# Watchdog.net
KiCad netlist of a schematic drawn in EasyEDA Pro
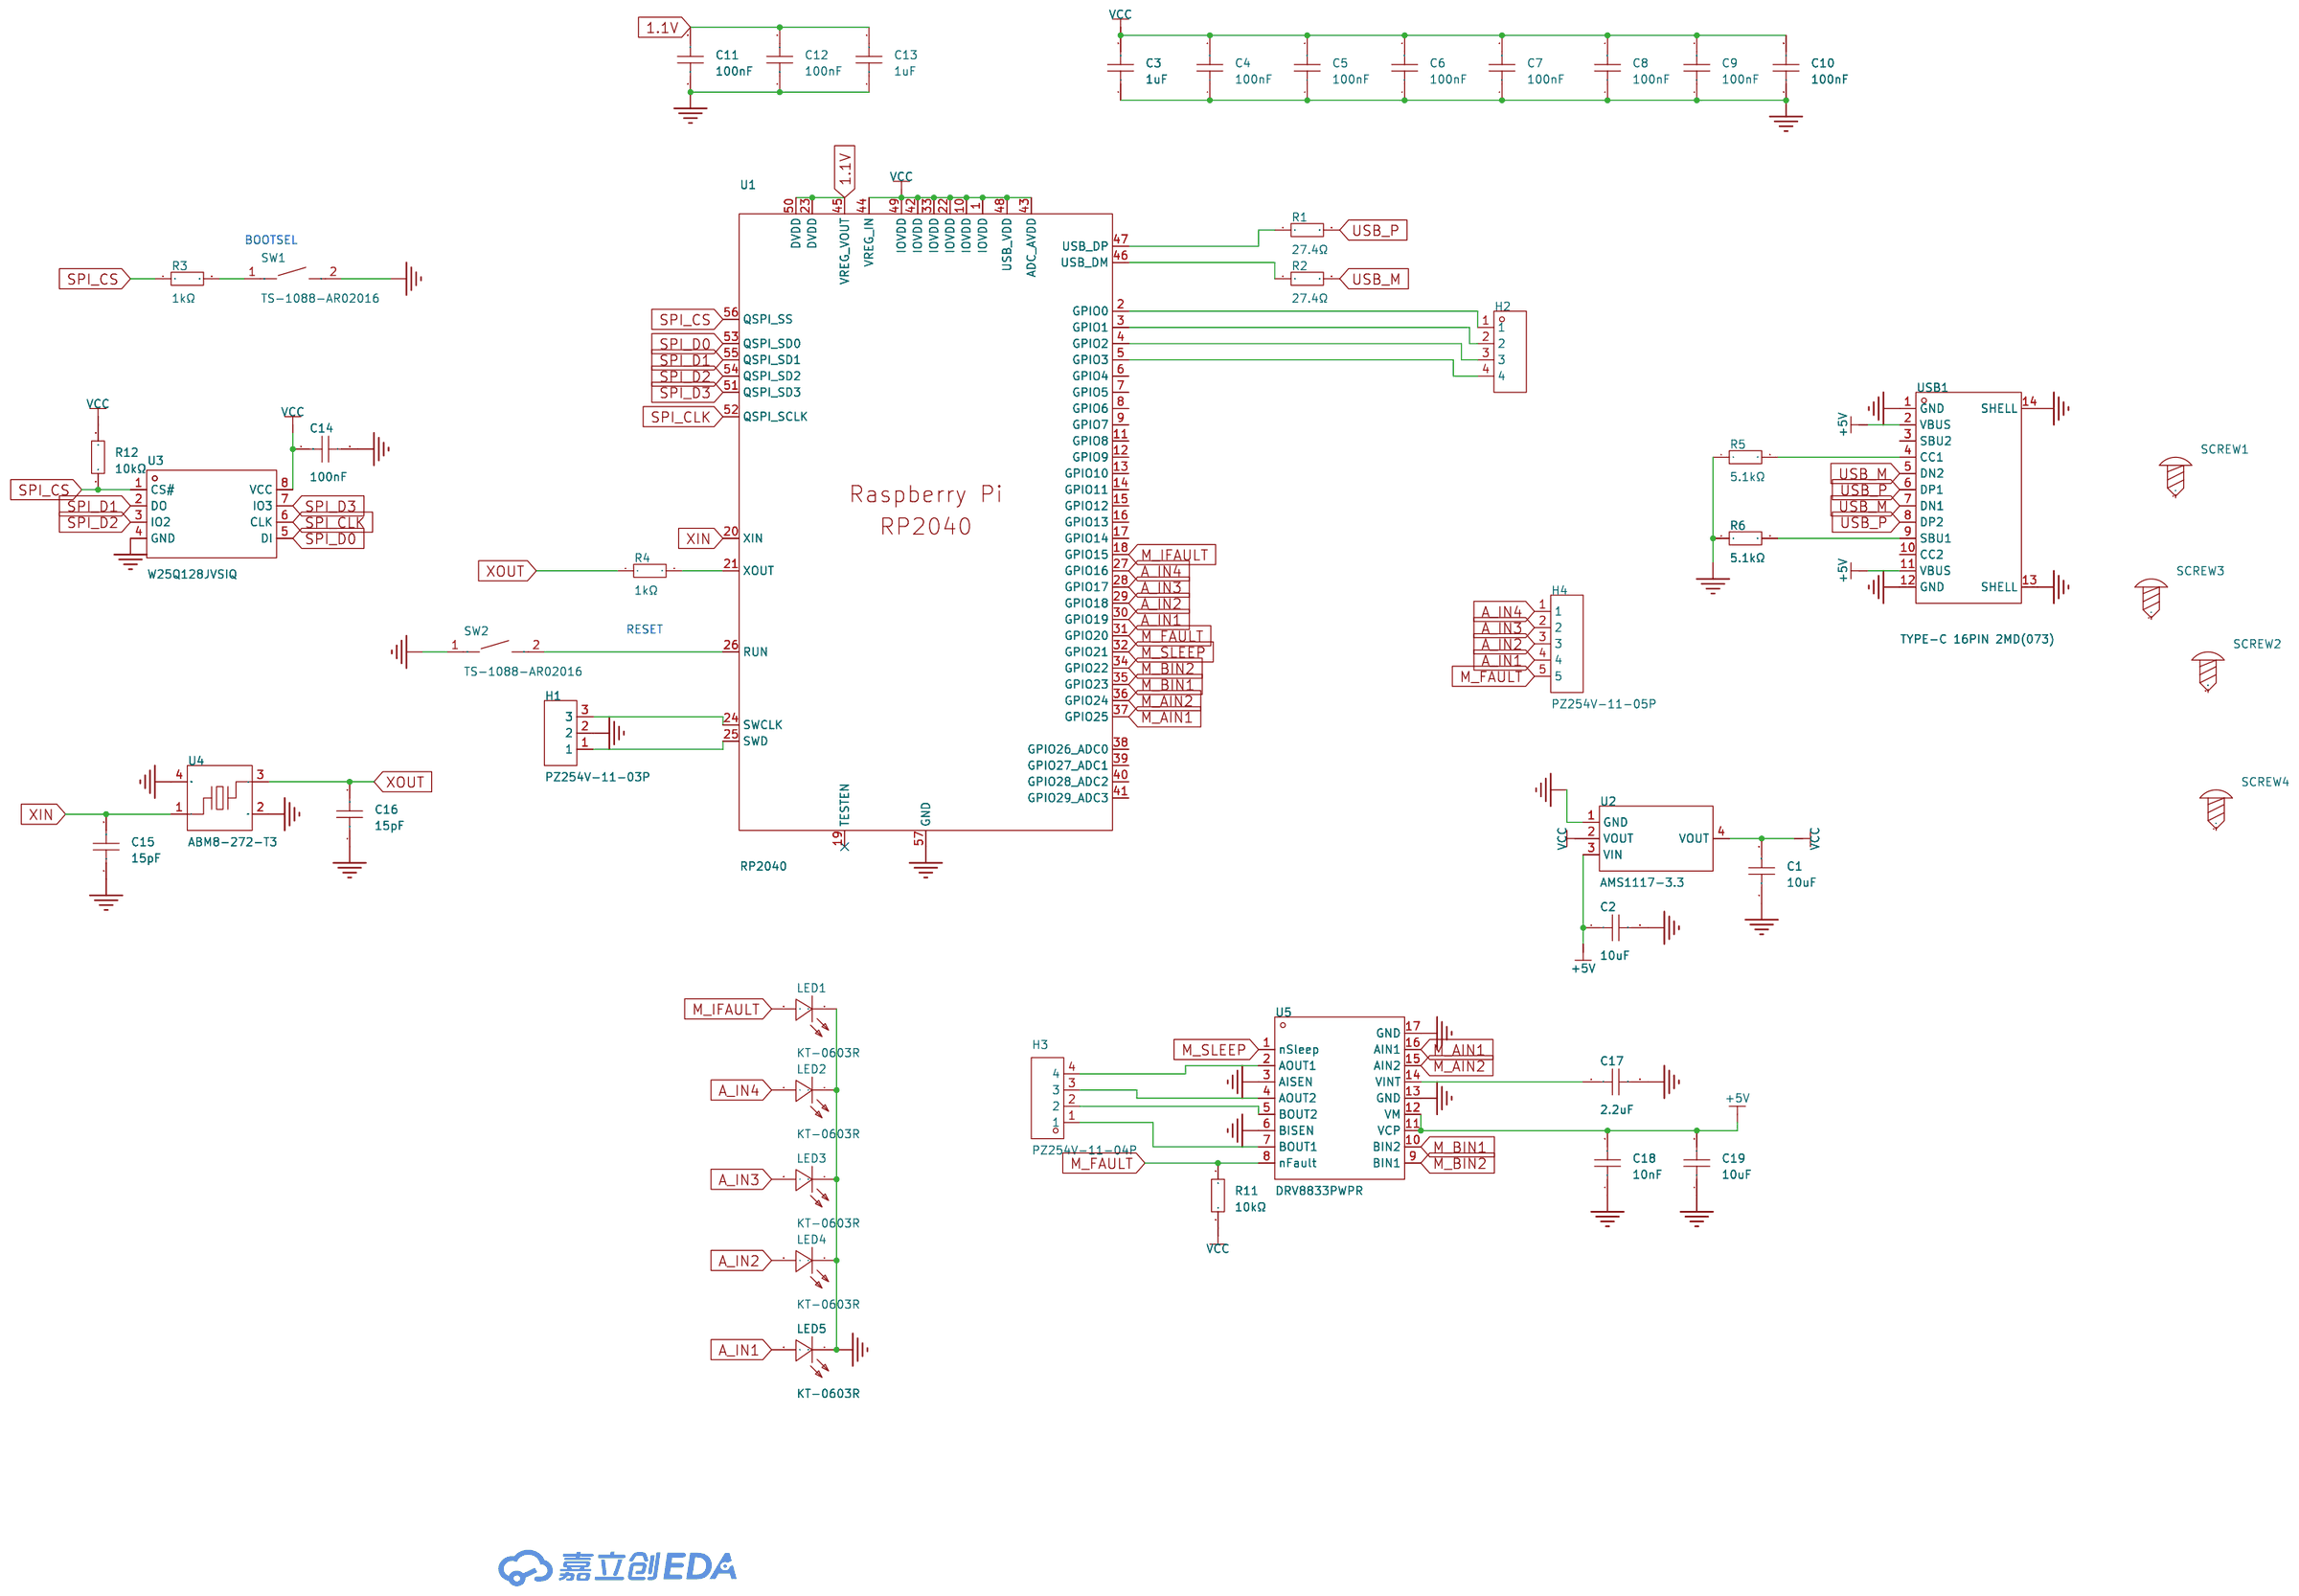
[diagram p0: schematic sheet]

(export (version "E")
  (design (tool "Eeschema 10.0.6"))
  (components
    (comp (ref "C1")
      (value "10uF")
      (footprint "easyedapro:C0603")
      (fields
        (field (name "Manufacturer Part") "CL05A106MQ5NUNC")
        (field (name "Manufacturer") "SAMSUNG(三星)")
      )
      (libsource (lib "easyedapro") (part "CapAcitance"))
    )
    (comp (ref "C2")
      (value "10uF")
      (footprint "easyedapro:C0603")
      (fields
        (field (name "Manufacturer Part") "CL05A106MQ5NUNC")
        (field (name "Manufacturer") "SAMSUNG(三星)")
      )
      (libsource (lib "easyedapro") (part "CapAcitance"))
    )
    (comp (ref "C3")
      (value "1uF")
      (footprint "easyedapro:C0603")
      (fields
        (field (name "Manufacturer Part") "CL05A105KA5NQNC")
        (field (name "Manufacturer") "SAMSUNG(三星)")
      )
      (libsource (lib "easyedapro") (part "CapAcitance"))
    )
    (comp (ref "C4")
      (value "100nF")
      (footprint "easyedapro:C0603")
      (fields
        (field (name "Manufacturer Part") "CL05B104KB54PNC")
        (field (name "Manufacturer") "SAMSUNG(三星)")
      )
      (libsource (lib "easyedapro") (part "CapAcitance"))
    )
    (comp (ref "C5")
      (value "100nF")
      (footprint "easyedapro:C0603")
      (fields
        (field (name "Manufacturer Part") "CL05B104KB54PNC")
        (field (name "Manufacturer") "SAMSUNG(三星)")
      )
      (libsource (lib "easyedapro") (part "CapAcitance"))
    )
    (comp (ref "C6")
      (value "100nF")
      (footprint "easyedapro:C0603")
      (fields
        (field (name "Manufacturer Part") "CL05B104KB54PNC")
        (field (name "Manufacturer") "SAMSUNG(三星)")
      )
      (libsource (lib "easyedapro") (part "CapAcitance"))
    )
    (comp (ref "C7")
      (value "100nF")
      (footprint "easyedapro:C0603")
      (fields
        (field (name "Manufacturer Part") "CL05B104KB54PNC")
        (field (name "Manufacturer") "SAMSUNG(三星)")
      )
      (libsource (lib "easyedapro") (part "CapAcitance"))
    )
    (comp (ref "C8")
      (value "100nF")
      (footprint "easyedapro:C0603")
      (fields
        (field (name "Manufacturer Part") "CL05B104KB54PNC")
        (field (name "Manufacturer") "SAMSUNG(三星)")
      )
      (libsource (lib "easyedapro") (part "CapAcitance"))
    )
    (comp (ref "C9")
      (value "100nF")
      (footprint "easyedapro:C0603")
      (fields
        (field (name "Manufacturer Part") "CL05B104KB54PNC")
        (field (name "Manufacturer") "SAMSUNG(三星)")
      )
      (libsource (lib "easyedapro") (part "CapAcitance"))
    )
    (comp (ref "C10")
      (value "100nF")
      (footprint "easyedapro:C0603")
      (fields
        (field (name "Manufacturer Part") "CL05B104KB54PNC")
        (field (name "Manufacturer") "SAMSUNG(三星)")
      )
      (libsource (lib "easyedapro") (part "CapAcitance"))
    )
    (comp (ref "C11")
      (value "100nF")
      (footprint "easyedapro:C0603")
      (fields
        (field (name "Manufacturer Part") "CL05B104KB54PNC")
        (field (name "Manufacturer") "SAMSUNG(三星)")
      )
      (libsource (lib "easyedapro") (part "CapAcitance"))
    )
    (comp (ref "C12")
      (value "100nF")
      (footprint "easyedapro:C0603")
      (fields
        (field (name "Manufacturer Part") "CL05B104KB54PNC")
        (field (name "Manufacturer") "SAMSUNG(三星)")
      )
      (libsource (lib "easyedapro") (part "CapAcitance"))
    )
    (comp (ref "C13")
      (value "1uF")
      (footprint "easyedapro:C0603")
      (fields
        (field (name "Manufacturer Part") "CL05A105KA5NQNC")
        (field (name "Manufacturer") "SAMSUNG(三星)")
      )
      (libsource (lib "easyedapro") (part "CapAcitance"))
    )
    (comp (ref "C14")
      (value "100nF")
      (footprint "easyedapro:C0603")
      (fields
        (field (name "Manufacturer Part") "CL05B104KB54PNC")
        (field (name "Manufacturer") "SAMSUNG(三星)")
      )
      (libsource (lib "easyedapro") (part "CapAcitance"))
    )
    (comp (ref "C15")
      (value "15pF")
      (footprint "easyedapro:C0603")
      (fields (field (name "Manufacturer Part") "0402CG150J500NT") (field (name "Manufacturer") "FH(风华)"))
      (libsource (lib "easyedapro") (part "CapAcitance"))
    )
    (comp (ref "C16")
      (value "15pF")
      (footprint "easyedapro:C0603")
      (fields (field (name "Manufacturer Part") "0402CG150J500NT") (field (name "Manufacturer") "FH(风华)"))
      (libsource (lib "easyedapro") (part "CapAcitance"))
    )
    (comp (ref "C17")
      (value "2.2uF")
      (footprint "easyedapro:C0603")
      (fields
        (field (name "Manufacturer Part") "CL05A225MQ5NSNC")
        (field (name "Manufacturer") "SAMSUNG(三星)")
      )
      (libsource (lib "easyedapro") (part "CapAcitance"))
    )
    (comp (ref "C18")
      (value "10nF")
      (footprint "easyedapro:C0603")
      (fields
        (field (name "Manufacturer Part") "CL05B103KB5NNNC")
        (field (name "Manufacturer") "SAMSUNG(三星)")
      )
      (libsource (lib "easyedapro") (part "CapAcitance"))
    )
    (comp (ref "C19")
      (value "10uF")
      (footprint "easyedapro:C0603")
      (fields
        (field (name "Manufacturer Part") "CL05A106MQ5NUNC")
        (field (name "Manufacturer") "SAMSUNG(三星)")
      )
      (libsource (lib "easyedapro") (part "CapAcitance"))
    )
    (comp (ref "H1")
      (value "PZ254V-11-03P")
      (footprint "easyedapro:HDR-TH_3P-P2.54-V-M")
      (fields (field (name "Manufacturer") "XFCN(兴飞)"))
      (libsource (lib "easyedapro") (part "PZ254V-11-03P_C2937625"))
    )
    (comp (ref "H2")
      (value "PZ254V-11-04P")
      (footprint "easyedapro:HDR-TH_4P-P2.54-V-M")
      (fields (field (name "Manufacturer") "XFCN(兴飞)"))
      (libsource (lib "easyedapro") (part "PZ254V-11-04P_C2691448"))
    )
    (comp (ref "H3")
      (value "PZ254V-11-04P")
      (footprint "easyedapro:HDR-TH_4P-P2.54-V-M")
      (fields (field (name "Manufacturer") "XFCN(兴飞)"))
      (libsource (lib "easyedapro") (part "PZ254V-11-04P_C2691448"))
    )
    (comp (ref "H4")
      (value "PZ254V-11-05P")
      (footprint "easyedapro:HDR-TH_5P-P2.54-V-M")
      (fields (field (name "Manufacturer") "XFCN(兴飞)"))
      (libsource (lib "easyedapro") (part "PZ254V-11-05P"))
    )
    (comp (ref "LED1")
      (value "KT-0603R")
      (footprint "easyedapro:LED0603-RD")
      (description "发光颜色:红色;功率:-;正向电流:-;主波长:-;二极管配置:-;透镜颜色:-;色温:-;发光角度:-;载带方式:-;工作温度:-40°C~+85°C;")
      (fields (field (name "Manufacturer") "KENTO"))
      (libsource (lib "easyedapro") (part "KT-0603R"))
    )
    (comp (ref "LED2")
      (value "KT-0603R")
      (footprint "easyedapro:LED0603-RD")
      (description "发光颜色:红色;功率:-;正向电流:-;主波长:-;二极管配置:-;透镜颜色:-;色温:-;发光角度:-;载带方式:-;工作温度:-40°C~+85°C;")
      (fields (field (name "Manufacturer") "KENTO"))
      (libsource (lib "easyedapro") (part "KT-0603R"))
    )
    (comp (ref "LED3")
      (value "KT-0603R")
      (footprint "easyedapro:LED0603-RD")
      (description "发光颜色:红色;功率:-;正向电流:-;主波长:-;二极管配置:-;透镜颜色:-;色温:-;发光角度:-;载带方式:-;工作温度:-40°C~+85°C;")
      (fields (field (name "Manufacturer") "KENTO"))
      (libsource (lib "easyedapro") (part "KT-0603R"))
    )
    (comp (ref "LED4")
      (value "KT-0603R")
      (footprint "easyedapro:LED0603-RD")
      (description "发光颜色:红色;功率:-;正向电流:-;主波长:-;二极管配置:-;透镜颜色:-;色温:-;发光角度:-;载带方式:-;工作温度:-40°C~+85°C;")
      (fields (field (name "Manufacturer") "KENTO"))
      (libsource (lib "easyedapro") (part "KT-0603R"))
    )
    (comp (ref "LED5")
      (value "KT-0603R")
      (footprint "easyedapro:LED0603-RD")
      (description "发光颜色:红色;功率:-;正向电流:-;主波长:-;二极管配置:-;透镜颜色:-;色温:-;发光角度:-;载带方式:-;工作温度:-40°C~+85°C;")
      (fields (field (name "Manufacturer") "KENTO"))
      (libsource (lib "easyedapro") (part "KT-0603R"))
    )
    (comp (ref "R1")
      (value "27.4Ω")
      (footprint "easyedapro:R0603")
      (fields (field (name "Manufacturer Part") "WR04X27R4FTL") (field (name "Manufacturer") "Walsin(华新科)"))
      (libsource (lib "easyedapro") (part "电阻"))
    )
    (comp (ref "R2")
      (value "27.4Ω")
      (footprint "easyedapro:R0603")
      (fields (field (name "Manufacturer Part") "WR04X27R4FTL") (field (name "Manufacturer") "Walsin(华新科)"))
      (libsource (lib "easyedapro") (part "电阻"))
    )
    (comp (ref "R3")
      (value "1kΩ")
      (footprint "easyedapro:R0603")
      (fields
        (field (name "Manufacturer Part") "0402WGF1001TCE")
        (field (name "Manufacturer") "UNI-ROYAL(厚声)")
      )
      (libsource (lib "easyedapro") (part "电阻"))
    )
    (comp (ref "R4")
      (value "1kΩ")
      (footprint "easyedapro:R0603")
      (fields
        (field (name "Manufacturer Part") "0402WGF1001TCE")
        (field (name "Manufacturer") "UNI-ROYAL(厚声)")
      )
      (libsource (lib "easyedapro") (part "电阻"))
    )
    (comp (ref "R5")
      (value "5.1kΩ")
      (footprint "easyedapro:R0603")
      (fields
        (field (name "Manufacturer Part") "0402WGF5101TCE")
        (field (name "Manufacturer") "UNI-ROYAL(厚声)")
      )
      (libsource (lib "easyedapro") (part "电阻"))
    )
    (comp (ref "R6")
      (value "5.1kΩ")
      (footprint "easyedapro:R0603")
      (fields
        (field (name "Manufacturer Part") "0402WGF5101TCE")
        (field (name "Manufacturer") "UNI-ROYAL(厚声)")
      )
      (libsource (lib "easyedapro") (part "电阻"))
    )
    (comp (ref "R11")
      (value "10kΩ")
      (footprint "easyedapro:R0603")
      (fields
        (field (name "Manufacturer Part") "0402WGF1002TCE")
        (field (name "Manufacturer") "UNI-ROYAL(厚声)")
      )
      (libsource (lib "easyedapro") (part "电阻"))
    )
    (comp (ref "R12")
      (value "10kΩ")
      (footprint "easyedapro:R0603")
      (fields
        (field (name "Manufacturer Part") "0402WGF1002TCE")
        (field (name "Manufacturer") "UNI-ROYAL(厚声)")
      )
      (libsource (lib "easyedapro") (part "电阻"))
    )
    (comp (ref "SCREW1")
      (value "~")
      (footprint "easyedapro:M3螺丝")
      (libsource (lib "easyedapro") (part "螺丝孔"))
    )
    (comp (ref "SCREW2")
      (value "~")
      (footprint "easyedapro:M3螺丝")
      (libsource (lib "easyedapro") (part "螺丝孔"))
    )
    (comp (ref "SCREW3")
      (value "~")
      (footprint "easyedapro:M3螺丝")
      (libsource (lib "easyedapro") (part "螺丝孔"))
    )
    (comp (ref "SCREW4")
      (value "~")
      (footprint "easyedapro:M3螺丝")
      (libsource (lib "easyedapro") (part "螺丝孔"))
    )
    (comp (ref "SW1")
      (value "TS-1088-AR02016")
      (footprint "easyedapro:SW-SMD_L3.9-W3.0-P4.45")
      (fields (field (name "Manufacturer") "XUNPU(讯普)"))
      (libsource (lib "easyedapro") (part "TS-1088-AR02016"))
    )
    (comp (ref "SW2")
      (value "TS-1088-AR02016")
      (footprint "easyedapro:SW-SMD_L3.9-W3.0-P4.45")
      (fields (field (name "Manufacturer") "XUNPU(讯普)"))
      (libsource (lib "easyedapro") (part "TS-1088-AR02016"))
    )
    (comp (ref "U1")
      (value "RP2040")
      (footprint "easyedapro:LQFN-56_L7.0-W7.0-P0.4-EP")
      (description "CPU内核:-;CPU最大主频:133MHz;应用领域:-;")
      (fields (field (name "Manufacturer") "Raspberry Pi(树莓派)"))
      (libsource (lib "easyedapro") (part "RP2040"))
    )
    (comp (ref "U2")
      (value "AMS1117-3.3")
      (footprint "easyedapro:SOT-223-3_L6.5-W3.4-P2.30-LS7.0-BR")
      (description "输出类型:固定;工作电压:16V;输出电压:3.3V;输出电流:1A;电源纹波抑制比(PSRR):72dB@(120Hz);输出极性:正极;")
      (fields (field (name "Manufacturer") "AMS"))
      (libsource (lib "easyedapro") (part "AMS1117-3.3"))
    )
    (comp (ref "U3")
      (value "W25Q128JVSIQ")
      (footprint "easyedapro:SOIC-8_L5.3-W5.3-P1.27-LS8.0-BL")
      (description "接口类型:SPI;存储容量:128Mbit;时钟频率(fc):133MHz;")
      (fields (field (name "Manufacturer") "WINBOND(华邦)"))
      (libsource (lib "easyedapro") (part "W25Q128JVSIQTR"))
    )
    (comp (ref "U4")
      (value "ABM8-272-T3")
      (footprint "easyedapro:CRYSTAL-SMD_4P-L3.2-W2.5-BL")
      (description "推荐配套使用产品C20625731    ABM8-272-T3 与 C2040   RP2040")
      (fields (field (name "Manufacturer") "ABRACON"))
      (libsource (lib "easyedapro") (part "ABM8-272-T3_C20625731"))
    )
    (comp (ref "U5")
      (value "DRV8833PWPR")
      (footprint "easyedapro:TSSOP-16_L5.0-W4.4-P0.65-LS6.4-BL-EP")
      (description "DRV8833 具有电流调节功能的 10.8V、2A、双通道 H 桥电机驱动器")
      (fields (field (name "Manufacturer") "TI(德州仪器)"))
      (libsource (lib "easyedapro") (part "DRV8833PWP"))
    )
    (comp (ref "USB1")
      (value "TYPE-C 16PIN 2MD(073)")
      (footprint "easyedapro:USB-C-SMD_TYPE-C-6PIN-2MD-073")
      (description "连接器类型:Type-C;标准:USB 3.1;公母:母;安装方式:卧贴;触点数量:16P;端口数量:1;额定电流 - 电源:5A;工作温度范围:-25°C~+85°C;")
      (fields (field (name "Manufacturer") "SHOU HAN(首韩)"))
      (libsource (lib "easyedapro") (part "TYPE-C 16PIN 2MD(073)"))
    )
  )
  (nets
    (net (code "1") (name "+5V") (class "Default")
      (node (ref "C18") (pin "2") (pinfunction "2_2") (pintype "input"))
      (node (ref "C19") (pin "2") (pinfunction "2_2") (pintype "input"))
      (node (ref "C2") (pin "1") (pinfunction "1_1") (pintype "input"))
      (node (ref "U2") (pin "3") (pinfunction "VIN_3") (pintype "unspecified"))
      (node (ref "U5") (pin "11") (pinfunction "VCP_11") (pintype "unspecified"))
      (node (ref "U5") (pin "12") (pinfunction "VM_12") (pintype "unspecified"))
      (node (ref "USB1") (pin "11") (pinfunction "VBUS_11") (pintype "unspecified"))
      (node (ref "USB1") (pin "2") (pinfunction "VBUS_2") (pintype "unspecified"))
    )
    (net (code "2") (name "1.1V") (class "Default")
      (node (ref "C11") (pin "2") (pinfunction "2_2") (pintype "input"))
      (node (ref "C12") (pin "2") (pinfunction "2_2") (pintype "input"))
      (node (ref "C13") (pin "2") (pinfunction "2_2") (pintype "input"))
      (node (ref "U1") (pin "23") (pinfunction "DVDD_23") (pintype "bidirectional"))
      (node (ref "U1") (pin "45") (pinfunction "VREG_VOUT_45") (pintype "bidirectional"))
      (node (ref "U1") (pin "50") (pinfunction "DVDD_50") (pintype "bidirectional"))
    )
    (net (code "3") (name "A_IN1") (class "Default")
      (node (ref "H4") (pin "4") (pinfunction "4_4") (pintype "unspecified"))
      (node (ref "LED5") (pin "2") (pinfunction "A_2") (pintype "unspecified"))
      (node (ref "U1") (pin "30") (pinfunction "GPIO19_30") (pintype "bidirectional"))
    )
    (net (code "4") (name "A_IN2") (class "Default")
      (node (ref "H4") (pin "3") (pinfunction "3_3") (pintype "unspecified"))
      (node (ref "LED4") (pin "2") (pinfunction "A_2") (pintype "unspecified"))
      (node (ref "U1") (pin "29") (pinfunction "GPIO18_29") (pintype "bidirectional"))
    )
    (net (code "5") (name "A_IN3") (class "Default")
      (node (ref "H4") (pin "2") (pinfunction "2_2") (pintype "unspecified"))
      (node (ref "LED3") (pin "2") (pinfunction "A_2") (pintype "unspecified"))
      (node (ref "U1") (pin "28") (pinfunction "GPIO17_28") (pintype "bidirectional"))
    )
    (net (code "6") (name "A_IN4") (class "Default")
      (node (ref "H4") (pin "1") (pinfunction "1_1") (pintype "unspecified"))
      (node (ref "LED2") (pin "2") (pinfunction "A_2") (pintype "unspecified"))
      (node (ref "U1") (pin "27") (pinfunction "GPIO16_27") (pintype "bidirectional"))
    )
    (net (code "7") (name "GND") (class "Default")
      (node (ref "C1") (pin "1") (pinfunction "1_1") (pintype "input"))
      (node (ref "C10") (pin "1") (pinfunction "1_1") (pintype "input"))
      (node (ref "C11") (pin "1") (pinfunction "1_1") (pintype "input"))
      (node (ref "C12") (pin "1") (pinfunction "1_1") (pintype "input"))
      (node (ref "C13") (pin "1") (pinfunction "1_1") (pintype "input"))
      (node (ref "C14") (pin "2") (pinfunction "2_2") (pintype "input"))
      (node (ref "C15") (pin "1") (pinfunction "1_1") (pintype "input"))
      (node (ref "C16") (pin "1") (pinfunction "1_1") (pintype "input"))
      (node (ref "C17") (pin "2") (pinfunction "2_2") (pintype "input"))
      (node (ref "C18") (pin "1") (pinfunction "1_1") (pintype "input"))
      (node (ref "C19") (pin "1") (pinfunction "1_1") (pintype "input"))
      (node (ref "C2") (pin "2") (pinfunction "2_2") (pintype "input"))
      (node (ref "C3") (pin "1") (pinfunction "1_1") (pintype "input"))
      (node (ref "C4") (pin "1") (pinfunction "1_1") (pintype "input"))
      (node (ref "C5") (pin "1") (pinfunction "1_1") (pintype "input"))
      (node (ref "C6") (pin "1") (pinfunction "1_1") (pintype "input"))
      (node (ref "C7") (pin "1") (pinfunction "1_1") (pintype "input"))
      (node (ref "C8") (pin "1") (pinfunction "1_1") (pintype "input"))
      (node (ref "C9") (pin "1") (pinfunction "1_1") (pintype "input"))
      (node (ref "H1") (pin "2") (pinfunction "2_2") (pintype "unspecified"))
      (node (ref "LED1") (pin "1") (pinfunction "K_1") (pintype "unspecified"))
      (node (ref "LED2") (pin "1") (pinfunction "K_1") (pintype "unspecified"))
      (node (ref "LED3") (pin "1") (pinfunction "K_1") (pintype "unspecified"))
      (node (ref "LED4") (pin "1") (pinfunction "K_1") (pintype "unspecified"))
      (node (ref "LED5") (pin "1") (pinfunction "K_1") (pintype "unspecified"))
      (node (ref "R5") (pin "1") (pinfunction "1_1") (pintype "input"))
      (node (ref "R6") (pin "1") (pinfunction "1_1") (pintype "input"))
      (node (ref "SW1") (pin "2") (pinfunction "2_2") (pintype "unspecified"))
      (node (ref "SW2") (pin "1") (pinfunction "1_1") (pintype "unspecified"))
      (node (ref "U1") (pin "57") (pinfunction "GND_57") (pintype "bidirectional"))
      (node (ref "U2") (pin "1") (pinfunction "GND_1") (pintype "unspecified"))
      (node (ref "U3") (pin "4") (pinfunction "GND_4") (pintype "unspecified"))
      (node (ref "U4") (pin "2") (pinfunction "GND_2") (pintype "input"))
      (node (ref "U4") (pin "4") (pinfunction "GND_4") (pintype "input"))
      (node (ref "U5") (pin "13") (pinfunction "GND_13") (pintype "unspecified"))
      (node (ref "U5") (pin "17") (pinfunction "GND_17") (pintype "unspecified"))
      (node (ref "U5") (pin "3") (pinfunction "AISEN_3") (pintype "unspecified"))
      (node (ref "U5") (pin "6") (pinfunction "BISEN_6") (pintype "unspecified"))
      (node (ref "USB1") (pin "1") (pinfunction "GND_1") (pintype "unspecified"))
      (node (ref "USB1") (pin "12") (pinfunction "GND_12") (pintype "unspecified"))
      (node (ref "USB1") (pin "13") (pinfunction "SHELL_13") (pintype "unspecified"))
      (node (ref "USB1") (pin "14") (pinfunction "SHELL_14") (pintype "unspecified"))
    )
    (net (code "8") (name "M_AIN1") (class "Default")
      (node (ref "U1") (pin "37") (pinfunction "GPIO25_37") (pintype "bidirectional"))
      (node (ref "U5") (pin "16") (pinfunction "AIN1_16") (pintype "unspecified"))
    )
    (net (code "9") (name "M_AIN2") (class "Default")
      (node (ref "U1") (pin "36") (pinfunction "GPIO24_36") (pintype "bidirectional"))
      (node (ref "U5") (pin "15") (pinfunction "AIN2_15") (pintype "unspecified"))
    )
    (net (code "10") (name "M_BIN1") (class "Default")
      (node (ref "U1") (pin "35") (pinfunction "GPIO23_35") (pintype "bidirectional"))
      (node (ref "U5") (pin "10") (pinfunction "BIN2_10") (pintype "unspecified"))
    )
    (net (code "11") (name "M_BIN2") (class "Default")
      (node (ref "U1") (pin "34") (pinfunction "GPIO22_34") (pintype "bidirectional"))
      (node (ref "U5") (pin "9") (pinfunction "BIN1_9") (pintype "unspecified"))
    )
    (net (code "12") (name "M_FAULT") (class "Default")
      (node (ref "H4") (pin "5") (pinfunction "5_5") (pintype "unspecified"))
      (node (ref "R11") (pin "2") (pinfunction "2_2") (pintype "input"))
      (node (ref "U1") (pin "31") (pinfunction "GPIO20_31") (pintype "bidirectional"))
      (node (ref "U5") (pin "8") (pinfunction "nFault_8") (pintype "unspecified"))
    )
    (net (code "13") (name "M_IFAULT") (class "Default")
      (node (ref "LED1") (pin "2") (pinfunction "A_2") (pintype "unspecified"))
      (node (ref "U1") (pin "18") (pinfunction "GPIO15_18") (pintype "bidirectional"))
    )
    (net (code "14") (name "M_SLEEP") (class "Default")
      (node (ref "U1") (pin "32") (pinfunction "GPIO21_32") (pintype "bidirectional"))
      (node (ref "U5") (pin "1") (pinfunction "nSleep_1") (pintype "unspecified"))
    )
    (net (code "15") (name "Net-(R3-Pad2)") (class "Default")
      (node (ref "R3") (pin "2") (pinfunction "2_2") (pintype "input"))
      (node (ref "SW1") (pin "1") (pinfunction "1_1") (pintype "unspecified"))
    )
    (net (code "16") (name "Net-(U1-GPIO0)") (class "Default")
      (node (ref "H2") (pin "1") (pinfunction "1_1") (pintype "unspecified"))
      (node (ref "U1") (pin "2") (pinfunction "GPIO0_2") (pintype "bidirectional"))
    )
    (net (code "17") (name "Net-(U1-GPIO1)") (class "Default")
      (node (ref "H2") (pin "2") (pinfunction "2_2") (pintype "unspecified"))
      (node (ref "U1") (pin "3") (pinfunction "GPIO1_3") (pintype "bidirectional"))
    )
    (net (code "18") (name "Net-(U1-GPIO2)") (class "Default")
      (node (ref "H2") (pin "3") (pinfunction "3_3") (pintype "unspecified"))
      (node (ref "U1") (pin "4") (pinfunction "GPIO2_4") (pintype "bidirectional"))
    )
    (net (code "19") (name "Net-(U1-GPIO3)") (class "Default")
      (node (ref "H2") (pin "4") (pinfunction "4_4") (pintype "unspecified"))
      (node (ref "U1") (pin "5") (pinfunction "GPIO3_5") (pintype "bidirectional"))
    )
    (net (code "20") (name "Net-(U1-RUN)") (class "Default")
      (node (ref "SW2") (pin "2") (pinfunction "2_2") (pintype "unspecified"))
      (node (ref "U1") (pin "26") (pinfunction "RUN_26") (pintype "input"))
    )
    (net (code "21") (name "Net-(U1-SWCLK)") (class "Default")
      (node (ref "H1") (pin "3") (pinfunction "3_3") (pintype "unspecified"))
      (node (ref "U1") (pin "24") (pinfunction "SWCLK_24") (pintype "output"))
    )
    (net (code "22") (name "Net-(U1-SWD)") (class "Default")
      (node (ref "H1") (pin "1") (pinfunction "1_1") (pintype "unspecified"))
      (node (ref "U1") (pin "25") (pinfunction "SWD_25") (pintype "bidirectional"))
    )
    (net (code "23") (name "Net-(U1-USB_DM)") (class "Default")
      (node (ref "R2") (pin "1") (pinfunction "1_1") (pintype "input"))
      (node (ref "U1") (pin "46") (pinfunction "USB_DM_46") (pintype "bidirectional"))
    )
    (net (code "24") (name "Net-(U1-USB_DP)") (class "Default")
      (node (ref "R1") (pin "1") (pinfunction "1_1") (pintype "input"))
      (node (ref "U1") (pin "47") (pinfunction "USB_DP_47") (pintype "bidirectional"))
    )
    (net (code "25") (name "Net-(U1-XOUT)") (class "Default")
      (node (ref "R4") (pin "2") (pinfunction "2_2") (pintype "input"))
      (node (ref "U1") (pin "21") (pinfunction "XOUT_21") (pintype "unspecified"))
    )
    (net (code "26") (name "Net-(U5-AOUT1)") (class "Default")
      (node (ref "H3") (pin "4") (pinfunction "4_4") (pintype "unspecified"))
      (node (ref "U5") (pin "2") (pinfunction "AOUT1_2") (pintype "unspecified"))
    )
    (net (code "27") (name "Net-(U5-AOUT2)") (class "Default")
      (node (ref "H3") (pin "3") (pinfunction "3_3") (pintype "unspecified"))
      (node (ref "U5") (pin "4") (pinfunction "AOUT2_4") (pintype "unspecified"))
    )
    (net (code "28") (name "Net-(U5-BOUT1)") (class "Default")
      (node (ref "H3") (pin "1") (pinfunction "1_1") (pintype "unspecified"))
      (node (ref "U5") (pin "7") (pinfunction "BOUT1_7") (pintype "unspecified"))
    )
    (net (code "29") (name "Net-(U5-BOUT2)") (class "Default")
      (node (ref "H3") (pin "2") (pinfunction "2_2") (pintype "unspecified"))
      (node (ref "U5") (pin "5") (pinfunction "BOUT2_5") (pintype "unspecified"))
    )
    (net (code "30") (name "Net-(U5-VINT)") (class "Default")
      (node (ref "C17") (pin "1") (pinfunction "1_1") (pintype "input"))
      (node (ref "U5") (pin "14") (pinfunction "VINT_14") (pintype "unspecified"))
    )
    (net (code "31") (name "Net-(USB1-CC1)") (class "Default")
      (node (ref "R5") (pin "2") (pinfunction "2_2") (pintype "input"))
      (node (ref "USB1") (pin "4") (pinfunction "CC1_4") (pintype "unspecified"))
    )
    (net (code "32") (name "Net-(USB1-SBU1)") (class "Default")
      (node (ref "R6") (pin "2") (pinfunction "2_2") (pintype "input"))
      (node (ref "USB1") (pin "9") (pinfunction "SBU1_9") (pintype "unspecified"))
    )
    (net (code "33") (name "SPI_CLK") (class "Default")
      (node (ref "U1") (pin "52") (pinfunction "QSPI_SCLK_52") (pintype "output"))
      (node (ref "U3") (pin "6") (pinfunction "CLK_6") (pintype "unspecified"))
    )
    (net (code "34") (name "SPI_CS") (class "Default")
      (node (ref "R12") (pin "1") (pinfunction "1_1") (pintype "input"))
      (node (ref "R3") (pin "1") (pinfunction "1_1") (pintype "input"))
      (node (ref "U1") (pin "56") (pinfunction "QSPI_SS_56") (pintype "bidirectional"))
      (node (ref "U3") (pin "1") (pinfunction "CS#_1") (pintype "unspecified"))
    )
    (net (code "35") (name "SPI_D0") (class "Default")
      (node (ref "U1") (pin "53") (pinfunction "QSPI_SD0_53") (pintype "bidirectional"))
      (node (ref "U3") (pin "5") (pinfunction "DI_5") (pintype "unspecified"))
    )
    (net (code "36") (name "SPI_D1") (class "Default")
      (node (ref "U1") (pin "55") (pinfunction "QSPI_SD1_55") (pintype "bidirectional"))
      (node (ref "U3") (pin "2") (pinfunction "DO_2") (pintype "unspecified"))
    )
    (net (code "37") (name "SPI_D2") (class "Default")
      (node (ref "U1") (pin "54") (pinfunction "QSPI_SD2_54") (pintype "bidirectional"))
      (node (ref "U3") (pin "3") (pinfunction "IO2_3") (pintype "unspecified"))
    )
    (net (code "38") (name "SPI_D3") (class "Default")
      (node (ref "U1") (pin "51") (pinfunction "QSPI_SD3_51") (pintype "bidirectional"))
      (node (ref "U3") (pin "7") (pinfunction "IO3_7") (pintype "unspecified"))
    )
    (net (code "39") (name "USB_M") (class "Default")
      (node (ref "R2") (pin "2") (pinfunction "2_2") (pintype "input"))
      (node (ref "USB1") (pin "5") (pinfunction "DN2_5") (pintype "unspecified"))
      (node (ref "USB1") (pin "7") (pinfunction "DN1_7") (pintype "unspecified"))
    )
    (net (code "40") (name "USB_P") (class "Default")
      (node (ref "R1") (pin "2") (pinfunction "2_2") (pintype "input"))
      (node (ref "USB1") (pin "6") (pinfunction "DP1_6") (pintype "unspecified"))
      (node (ref "USB1") (pin "8") (pinfunction "DP2_8") (pintype "unspecified"))
    )
    (net (code "41") (name "VCC") (class "Default")
      (node (ref "C1") (pin "2") (pinfunction "2_2") (pintype "input"))
      (node (ref "C10") (pin "2") (pinfunction "2_2") (pintype "input"))
      (node (ref "C14") (pin "1") (pinfunction "1_1") (pintype "input"))
      (node (ref "C3") (pin "2") (pinfunction "2_2") (pintype "input"))
      (node (ref "C4") (pin "2") (pinfunction "2_2") (pintype "input"))
      (node (ref "C5") (pin "2") (pinfunction "2_2") (pintype "input"))
      (node (ref "C6") (pin "2") (pinfunction "2_2") (pintype "input"))
      (node (ref "C7") (pin "2") (pinfunction "2_2") (pintype "input"))
      (node (ref "C8") (pin "2") (pinfunction "2_2") (pintype "input"))
      (node (ref "C9") (pin "2") (pinfunction "2_2") (pintype "input"))
      (node (ref "R11") (pin "1") (pinfunction "1_1") (pintype "input"))
      (node (ref "R12") (pin "2") (pinfunction "2_2") (pintype "input"))
      (node (ref "U1") (pin "1") (pinfunction "IOVDD_1") (pintype "bidirectional"))
      (node (ref "U1") (pin "10") (pinfunction "IOVDD_10") (pintype "bidirectional"))
      (node (ref "U1") (pin "22") (pinfunction "IOVDD_22") (pintype "bidirectional"))
      (node (ref "U1") (pin "33") (pinfunction "IOVDD_33") (pintype "bidirectional"))
      (node (ref "U1") (pin "42") (pinfunction "IOVDD_42") (pintype "bidirectional"))
      (node (ref "U1") (pin "43") (pinfunction "ADC_AVDD_43") (pintype "bidirectional"))
      (node (ref "U1") (pin "44") (pinfunction "VREG_IN_44") (pintype "bidirectional"))
      (node (ref "U1") (pin "48") (pinfunction "USB_VDD_48") (pintype "bidirectional"))
      (node (ref "U1") (pin "49") (pinfunction "IOVDD_49") (pintype "bidirectional"))
      (node (ref "U2") (pin "2") (pinfunction "VOUT_2") (pintype "unspecified"))
      (node (ref "U2") (pin "4") (pinfunction "VOUT_4") (pintype "unspecified"))
      (node (ref "U3") (pin "8") (pinfunction "VCC_8") (pintype "unspecified"))
    )
    (net (code "42") (name "XIN") (class "Default")
      (node (ref "C15") (pin "2") (pinfunction "2_2") (pintype "input"))
      (node (ref "U1") (pin "20") (pinfunction "XIN_20") (pintype "input"))
      (node (ref "U4") (pin "1") (pinfunction "1_1") (pintype "input"))
    )
    (net (code "43") (name "XOUT") (class "Default")
      (node (ref "C16") (pin "2") (pinfunction "2_2") (pintype "input"))
      (node (ref "R4") (pin "1") (pinfunction "1_1") (pintype "input"))
      (node (ref "U4") (pin "3") (pinfunction "3_3") (pintype "input"))
    )
    (net (code "44") (name "unconnected-(SCREW1-Pad1)") (class "Default")
      (node (ref "SCREW1") (pin "1") (pinfunction "1_1") (pintype "input"))
    )
    (net (code "45") (name "unconnected-(SCREW2-Pad1)") (class "Default")
      (node (ref "SCREW2") (pin "1") (pinfunction "1_1") (pintype "input"))
    )
    (net (code "46") (name "unconnected-(SCREW3-Pad1)") (class "Default")
      (node (ref "SCREW3") (pin "1") (pinfunction "1_1") (pintype "input"))
    )
    (net (code "47") (name "unconnected-(SCREW4-Pad1)") (class "Default")
      (node (ref "SCREW4") (pin "1") (pinfunction "1_1") (pintype "input"))
    )
    (net (code "48") (name "unconnected-(U1-GPIO4-Pad6)") (class "Default")
      (node (ref "U1") (pin "6") (pinfunction "GPIO4_6") (pintype "bidirectional"))
    )
    (net (code "49") (name "unconnected-(U1-GPIO5-Pad7)") (class "Default")
      (node (ref "U1") (pin "7") (pinfunction "GPIO5_7") (pintype "bidirectional"))
    )
    (net (code "50") (name "unconnected-(U1-GPIO6-Pad8)") (class "Default")
      (node (ref "U1") (pin "8") (pinfunction "GPIO6_8") (pintype "bidirectional"))
    )
    (net (code "51") (name "unconnected-(U1-GPIO7-Pad9)") (class "Default")
      (node (ref "U1") (pin "9") (pinfunction "GPIO7_9") (pintype "bidirectional"))
    )
    (net (code "52") (name "unconnected-(U1-GPIO8-Pad11)") (class "Default")
      (node (ref "U1") (pin "11") (pinfunction "GPIO8_11") (pintype "bidirectional"))
    )
    (net (code "53") (name "unconnected-(U1-GPIO9-Pad12)") (class "Default")
      (node (ref "U1") (pin "12") (pinfunction "GPIO9_12") (pintype "bidirectional"))
    )
    (net (code "54") (name "unconnected-(U1-GPIO10-Pad13)") (class "Default")
      (node (ref "U1") (pin "13") (pinfunction "GPIO10_13") (pintype "bidirectional"))
    )
    (net (code "55") (name "unconnected-(U1-GPIO11-Pad14)") (class "Default")
      (node (ref "U1") (pin "14") (pinfunction "GPIO11_14") (pintype "bidirectional"))
    )
    (net (code "56") (name "unconnected-(U1-GPIO12-Pad15)") (class "Default")
      (node (ref "U1") (pin "15") (pinfunction "GPIO12_15") (pintype "bidirectional"))
    )
    (net (code "57") (name "unconnected-(U1-GPIO13-Pad16)") (class "Default")
      (node (ref "U1") (pin "16") (pinfunction "GPIO13_16") (pintype "bidirectional"))
    )
    (net (code "58") (name "unconnected-(U1-GPIO14-Pad17)") (class "Default")
      (node (ref "U1") (pin "17") (pinfunction "GPIO14_17") (pintype "bidirectional"))
    )
    (net (code "59") (name "unconnected-(U1-GPIO26_ADC0-Pad38)") (class "Default")
      (node (ref "U1") (pin "38") (pinfunction "GPIO26_ADC0_38") (pintype "bidirectional"))
    )
    (net (code "60") (name "unconnected-(U1-GPIO27_ADC1-Pad39)") (class "Default")
      (node (ref "U1") (pin "39") (pinfunction "GPIO27_ADC1_39") (pintype "bidirectional"))
    )
    (net (code "61") (name "unconnected-(U1-GPIO28_ADC2-Pad40)") (class "Default")
      (node (ref "U1") (pin "40") (pinfunction "GPIO28_ADC2_40") (pintype "bidirectional"))
    )
    (net (code "62") (name "unconnected-(U1-GPIO29_ADC3-Pad41)") (class "Default")
      (node (ref "U1") (pin "41") (pinfunction "GPIO29_ADC3_41") (pintype "bidirectional"))
    )
    (net (code "63") (name "unconnected-(U1-TESTEN-Pad19)") (class "Default")
      (node (ref "U1") (pin "19") (pinfunction "TESTEN_19") (pintype "unspecified+no_connect"))
    )
    (net (code "64") (name "unconnected-(USB1-CC2-Pad10)") (class "Default")
      (node (ref "USB1") (pin "10") (pinfunction "CC2_10") (pintype "unspecified"))
    )
    (net (code "65") (name "unconnected-(USB1-SBU2-Pad3)") (class "Default")
      (node (ref "USB1") (pin "3") (pinfunction "SBU2_3") (pintype "unspecified"))
    )
  )
)
